# MotorController.net
KiCad netlist of a schematic drawn in EAGLE
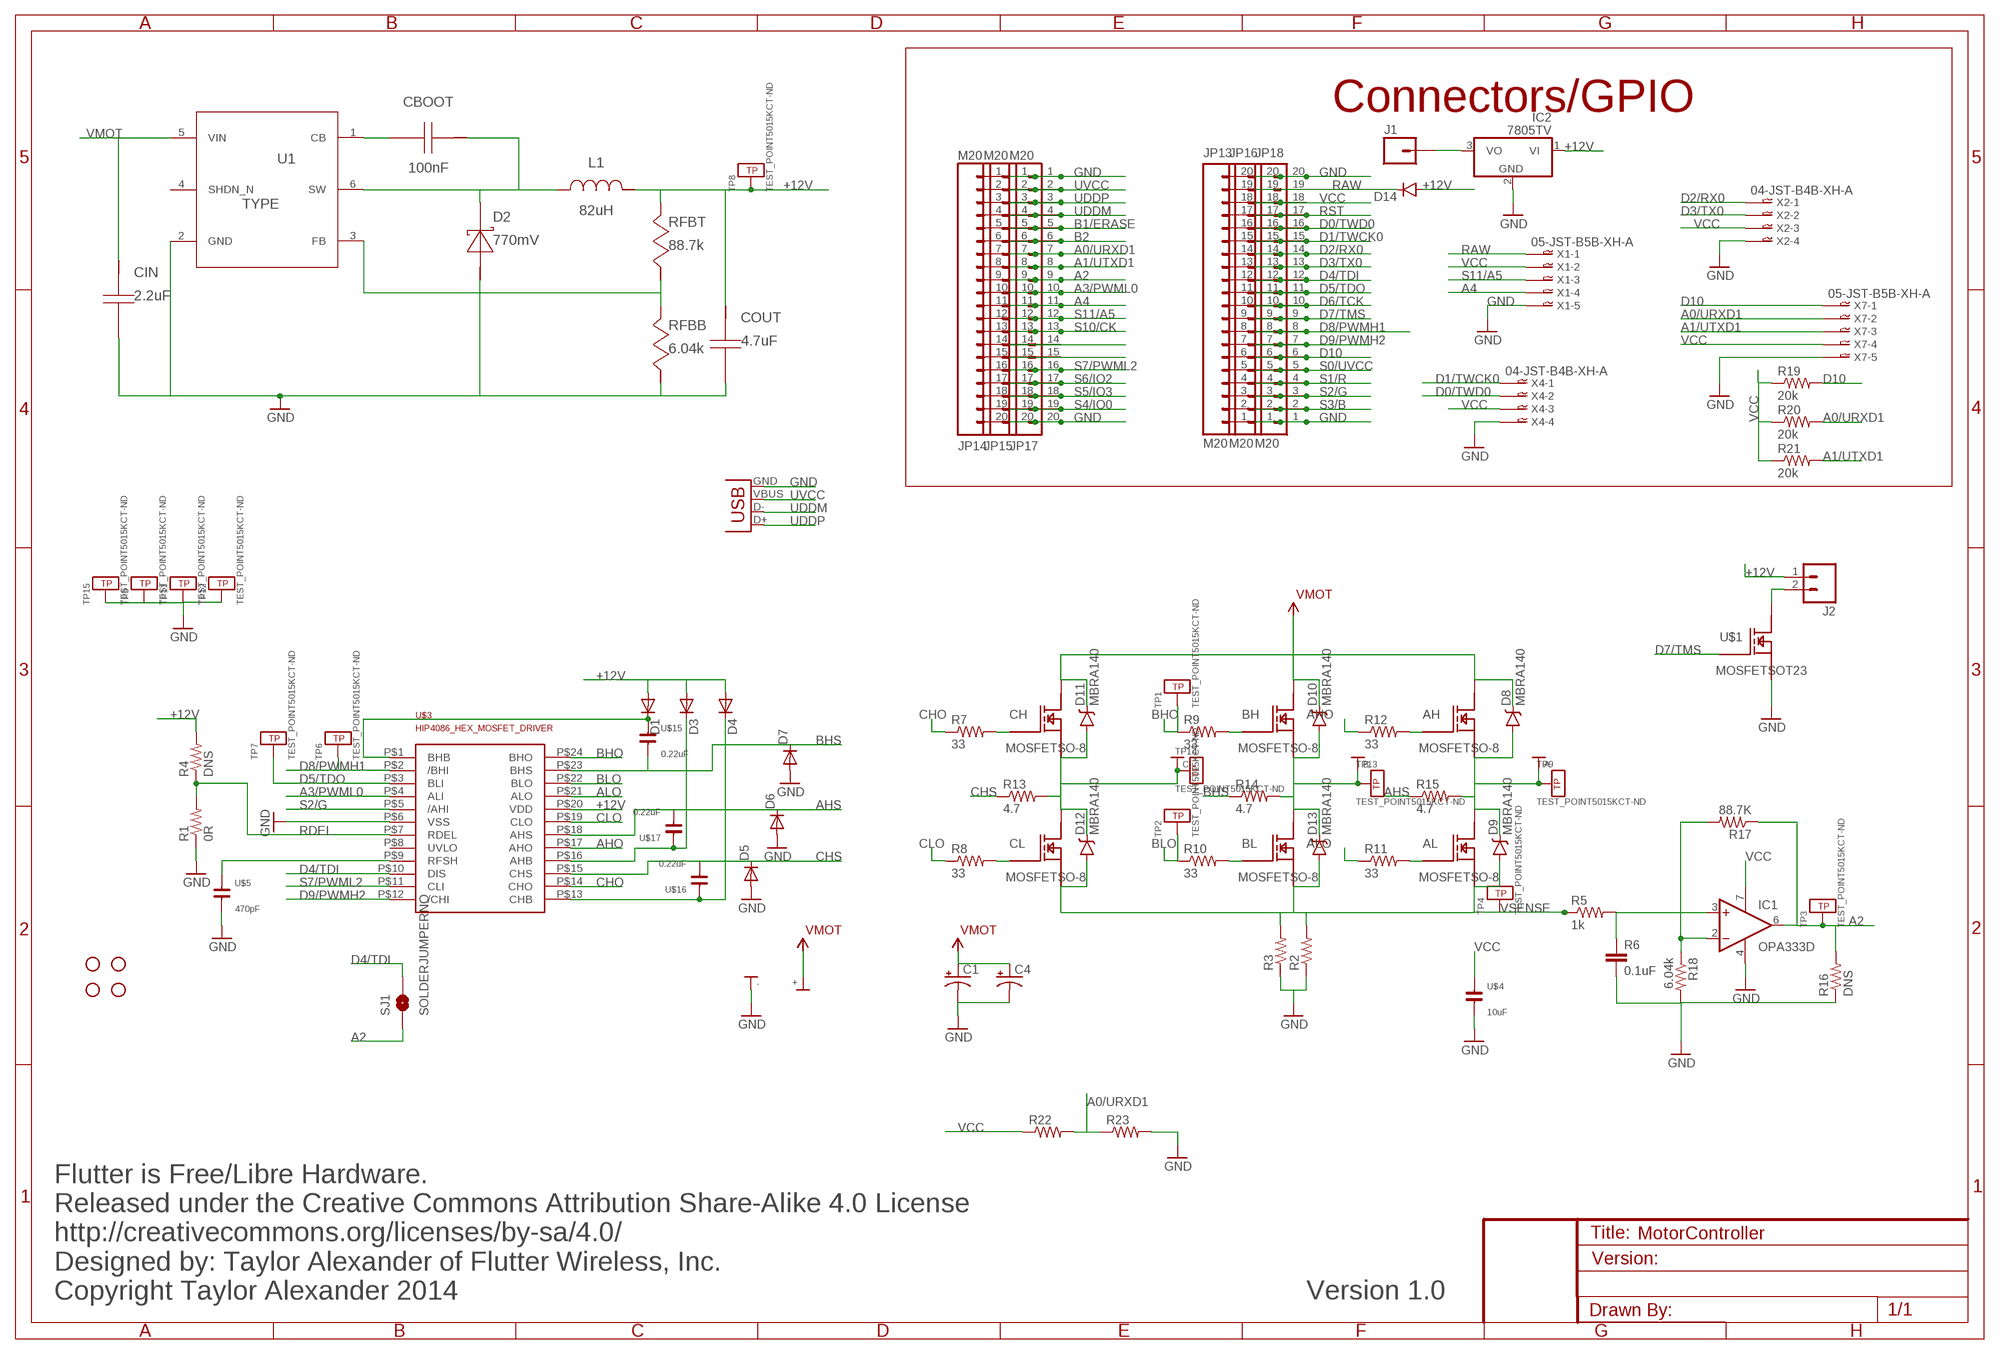
[diagram p0: schematic, sheet 1]

(export (version "E")
  (design (tool "Eeschema 10.0.6"))
  (components
    (comp (ref "+")
      (value "HIGHCURRENTPAD2")
      (footprint "eagle-import:HIGH_CURRENT_PAD2")
      (libsource (lib "eagle-import") (part "HIGHCURRENTPAD2"))
    )
    (comp (ref "-")
      (value "HIGHCURRENTPAD2")
      (footprint "eagle-import:HIGH_CURRENT_PAD2")
      (libsource (lib "eagle-import") (part "HIGHCURRENTPAD2"))
    )
    (comp (ref "A")
      (value "HIGHCURRENTPAD2")
      (footprint "eagle-import:HIGH_CURRENT_PAD2")
      (libsource (lib "eagle-import") (part "HIGHCURRENTPAD2"))
    )
    (comp (ref "AH")
      (value "MOSFETSO-8")
      (footprint "eagle-import:POWERPAK_S0-8")
      (libsource (lib "eagle-import") (part "MOSFETSO-8"))
    )
    (comp (ref "AL")
      (value "MOSFETSO-8")
      (footprint "eagle-import:POWERPAK_S0-8")
      (libsource (lib "eagle-import") (part "MOSFETSO-8"))
    )
    (comp (ref "B")
      (value "HIGHCURRENTPAD2")
      (footprint "eagle-import:HIGH_CURRENT_PAD2")
      (libsource (lib "eagle-import") (part "HIGHCURRENTPAD2"))
    )
    (comp (ref "BH")
      (value "MOSFETSO-8")
      (footprint "eagle-import:POWERPAK_S0-8")
      (libsource (lib "eagle-import") (part "MOSFETSO-8"))
    )
    (comp (ref "BL")
      (value "MOSFETSO-8")
      (footprint "eagle-import:POWERPAK_S0-8")
      (libsource (lib "eagle-import") (part "MOSFETSO-8"))
    )
    (comp (ref "C")
      (value "HIGHCURRENTPAD2")
      (footprint "eagle-import:HIGH_CURRENT_PAD2")
      (libsource (lib "eagle-import") (part "HIGHCURRENTPAD2"))
    )
    (comp (ref "C1")
      (value "CAPACITOR-POLARIZED")
      (footprint "eagle-import:CAP-6.5X18MM")
      (libsource (lib "eagle-import") (part "CAPACITOR-POLARIZED"))
    )
    (comp (ref "C4")
      (value "CAPACITOR-POLARIZED")
      (footprint "eagle-import:CAP-6.5X18MM")
      (libsource (lib "eagle-import") (part "CAPACITOR-POLARIZED"))
    )
    (comp (ref "CBOOT")
      (value "100nF")
      (footprint "eagle-import:0603")
      (fields (field (name "MANUFACTURER_PART_NUMBER") "GRM188R72A104KA35D"))
      (libsource (lib "eagle-import") (part "GRM188R72A104KA35D"))
    )
    (comp (ref "CH")
      (value "MOSFETSO-8")
      (footprint "eagle-import:POWERPAK_S0-8")
      (libsource (lib "eagle-import") (part "MOSFETSO-8"))
    )
    (comp (ref "CIN")
      (value "2.2uF")
      (footprint "eagle-import:1210")
      (fields (field (name "MANUFACTURER_PART_NUMBER") "C3225X7R2A225K230AB"))
      (libsource (lib "eagle-import") (part "C3225X7R2A225K230AB"))
    )
    (comp (ref "CL")
      (value "MOSFETSO-8")
      (footprint "eagle-import:POWERPAK_S0-8")
      (libsource (lib "eagle-import") (part "MOSFETSO-8"))
    )
    (comp (ref "COUT")
      (value "4.7uF")
      (footprint "eagle-import:0805")
      (fields (field (name "MANUFACTURER_PART_NUMBER") "GRM21BR61E475MA12L"))
      (libsource (lib "eagle-import") (part "GRM21BR61E475MA12L"))
    )
    (comp (ref "D1")
      (value "DIODESMA")
      (footprint "eagle-import:SMA-DIODE")
      (libsource (lib "eagle-import") (part "DIODESMA"))
    )
    (comp (ref "D2")
      (value "770mV")
      (footprint "eagle-import:POWERDI123")
      (fields (field (name "MANUFACTURER_PART_NUMBER") "DFLS1100-7"))
      (libsource (lib "eagle-import") (part "DFLS1100-7"))
    )
    (comp (ref "D3")
      (value "DIODESMA")
      (footprint "eagle-import:SMA-DIODE")
      (libsource (lib "eagle-import") (part "DIODESMA"))
    )
    (comp (ref "D4")
      (value "DIODESMA")
      (footprint "eagle-import:SMA-DIODE")
      (libsource (lib "eagle-import") (part "DIODESMA"))
    )
    (comp (ref "D5")
      (value "DIODESMA")
      (footprint "eagle-import:SMA-DIODE")
      (libsource (lib "eagle-import") (part "DIODESMA"))
    )
    (comp (ref "D6")
      (value "DIODESMA")
      (footprint "eagle-import:SMA-DIODE")
      (libsource (lib "eagle-import") (part "DIODESMA"))
    )
    (comp (ref "D7")
      (value "DIODESMA")
      (footprint "eagle-import:SMA-DIODE")
      (libsource (lib "eagle-import") (part "DIODESMA"))
    )
    (comp (ref "D8")
      (value "MBRA140")
      (footprint "eagle-import:SMA-DIODE")
      (libsource (lib "eagle-import") (part "DIODE-SCHOTTKY-MBRA140"))
    )
    (comp (ref "D9")
      (value "MBRA140")
      (footprint "eagle-import:SMA-DIODE")
      (libsource (lib "eagle-import") (part "DIODE-SCHOTTKY-MBRA140"))
    )
    (comp (ref "D10")
      (value "MBRA140")
      (footprint "eagle-import:SMA-DIODE")
      (libsource (lib "eagle-import") (part "DIODE-SCHOTTKY-MBRA140"))
    )
    (comp (ref "D11")
      (value "MBRA140")
      (footprint "eagle-import:SMA-DIODE")
      (libsource (lib "eagle-import") (part "DIODE-SCHOTTKY-MBRA140"))
    )
    (comp (ref "D12")
      (value "MBRA140")
      (footprint "eagle-import:SMA-DIODE")
      (libsource (lib "eagle-import") (part "DIODE-SCHOTTKY-MBRA140"))
    )
    (comp (ref "D13")
      (value "MBRA140")
      (footprint "eagle-import:SMA-DIODE")
      (libsource (lib "eagle-import") (part "DIODE-SCHOTTKY-MBRA140"))
    )
    (comp (ref "D14")
      (value "DIODESOD123")
      (footprint "eagle-import:SOD-123")
      (libsource (lib "eagle-import") (part "DIODESOD123"))
    )
    (comp (ref "IC1")
      (value "OPA333D")
      (footprint "eagle-import:SO08")
      (libsource (lib "eagle-import") (part "OPA333D"))
    )
    (comp (ref "IC2")
      (value "7805TV")
      (footprint "eagle-import:TO220V")
      (libsource (lib "eagle-import") (part "78TV05"))
    )
    (comp (ref "J1")
      (value "M01PTH")
      (footprint "eagle-import:1X01")
      (libsource (lib "eagle-import") (part "M01PTH"))
    )
    (comp (ref "J2")
      (value "M02PTH")
      (footprint "eagle-import:1X02")
      (libsource (lib "eagle-import") (part "M02PTH"))
    )
    (comp (ref "JP13")
      (value "M20")
      (footprint "eagle-import:1X20")
      (libsource (lib "eagle-import") (part "M20"))
    )
    (comp (ref "JP14")
      (value "M20")
      (footprint "eagle-import:1X20")
      (libsource (lib "eagle-import") (part "M20"))
    )
    (comp (ref "JP15")
      (value "M20")
      (footprint "eagle-import:1X20")
      (libsource (lib "eagle-import") (part "M20"))
    )
    (comp (ref "JP16")
      (value "M20")
      (footprint "eagle-import:1X20")
      (libsource (lib "eagle-import") (part "M20"))
    )
    (comp (ref "JP17")
      (value "M20")
      (footprint "eagle-import:1X20")
      (libsource (lib "eagle-import") (part "M20"))
    )
    (comp (ref "JP18")
      (value "M20")
      (footprint "eagle-import:1X20")
      (libsource (lib "eagle-import") (part "M20"))
    )
    (comp (ref "L1")
      (value "82uH")
      (footprint "eagle-import:ME3220")
      (fields (field (name "MANUFACTURER_PART_NUMBER") "ME3220-823KLB"))
      (libsource (lib "eagle-import") (part "ME3220-823KLB"))
    )
    (comp (ref "R1")
      (value "0R")
      (footprint "eagle-import:0603-RES")
      (libsource (lib "eagle-import") (part "RESISTOR0603"))
    )
    (comp (ref "R2")
      (value "RESISTOROHMITE")
      (footprint "eagle-import:OHMITE_FCSL64_CURRENT_SENSE_RESISTOR")
      (libsource (lib "eagle-import") (part "RESISTOROHMITE"))
    )
    (comp (ref "R3")
      (value "RESISTOROHMITE")
      (footprint "eagle-import:OHMITE_FCSL64_CURRENT_SENSE_RESISTOR")
      (libsource (lib "eagle-import") (part "RESISTOROHMITE"))
    )
    (comp (ref "R4")
      (value "DNS")
      (footprint "eagle-import:0603-RES")
      (libsource (lib "eagle-import") (part "RESISTOR0603"))
    )
    (comp (ref "R5")
      (value "1k")
      (footprint "eagle-import:0603-RES")
      (libsource (lib "eagle-import") (part "RESISTOR0603"))
    )
    (comp (ref "R6")
      (value "0.1uF")
      (footprint "eagle-import:0805")
      (libsource (lib "eagle-import") (part "CAP0805"))
    )
    (comp (ref "R7")
      (value "33")
      (footprint "eagle-import:0402-RES")
      (libsource (lib "eagle-import") (part "RESISTOR0402"))
    )
    (comp (ref "R8")
      (value "33")
      (footprint "eagle-import:0402-RES")
      (libsource (lib "eagle-import") (part "RESISTOR0402"))
    )
    (comp (ref "R9")
      (value "33")
      (footprint "eagle-import:0402-RES")
      (libsource (lib "eagle-import") (part "RESISTOR0402"))
    )
    (comp (ref "R10")
      (value "33")
      (footprint "eagle-import:0402-RES")
      (libsource (lib "eagle-import") (part "RESISTOR0402"))
    )
    (comp (ref "R11")
      (value "33")
      (footprint "eagle-import:0402-RES")
      (libsource (lib "eagle-import") (part "RESISTOR0402"))
    )
    (comp (ref "R12")
      (value "33")
      (footprint "eagle-import:0402-RES")
      (libsource (lib "eagle-import") (part "RESISTOR0402"))
    )
    (comp (ref "R13")
      (value "4.7")
      (footprint "eagle-import:0402-RES")
      (libsource (lib "eagle-import") (part "RESISTOR0402"))
    )
    (comp (ref "R14")
      (value "4.7")
      (footprint "eagle-import:0402-RES")
      (libsource (lib "eagle-import") (part "RESISTOR0402"))
    )
    (comp (ref "R15")
      (value "4.7")
      (footprint "eagle-import:0402-RES")
      (libsource (lib "eagle-import") (part "RESISTOR0402"))
    )
    (comp (ref "R16")
      (value "DNS")
      (footprint "eagle-import:0402-RES")
      (libsource (lib "eagle-import") (part "RESISTOR0402"))
    )
    (comp (ref "R17")
      (value "88.7K")
      (footprint "eagle-import:0402-RES")
      (libsource (lib "eagle-import") (part "RESISTOR0402"))
    )
    (comp (ref "R18")
      (value "6.04k")
      (footprint "eagle-import:0402-RES")
      (libsource (lib "eagle-import") (part "RESISTOR0402"))
    )
    (comp (ref "R19")
      (value "20k")
      (footprint "eagle-import:0402-RES")
      (libsource (lib "eagle-import") (part "RESISTOR0402"))
    )
    (comp (ref "R20")
      (value "20k")
      (footprint "eagle-import:0402-RES")
      (libsource (lib "eagle-import") (part "RESISTOR0402"))
    )
    (comp (ref "R21")
      (value "20k")
      (footprint "eagle-import:0402-RES")
      (libsource (lib "eagle-import") (part "RESISTOR0402"))
    )
    (comp (ref "R22")
      (value "RESISTOR0603")
      (footprint "eagle-import:0603-RES")
      (libsource (lib "eagle-import") (part "RESISTOR0603"))
    )
    (comp (ref "R23")
      (value "RESISTOR0603")
      (footprint "eagle-import:0603-RES")
      (libsource (lib "eagle-import") (part "RESISTOR0603"))
    )
    (comp (ref "RFBB")
      (value "6.04k")
      (footprint "eagle-import:0402")
      (fields
        (field (name "MANUFACTURER_PART_NUMBER") "CRCW04026K04FKED")
        (field (name "POWER") "0.063")
        (field (name "TOLERANCE") "1.0")
      )
      (libsource (lib "eagle-import") (part "CRCW04026K04FKED"))
    )
    (comp (ref "RFBT")
      (value "88.7k")
      (footprint "eagle-import:0402")
      (fields
        (field (name "MANUFACTURER_PART_NUMBER") "CRCW040288K7FKED")
        (field (name "POWER") "0.063")
        (field (name "TOLERANCE") "1.0")
      )
      (libsource (lib "eagle-import") (part "CRCW040288K7FKED"))
    )
    (comp (ref "SJ1")
      (value "SOLDERJUMPERNO")
      (footprint "eagle-import:SJ_2S-NO")
      (libsource (lib "eagle-import") (part "SOLDERJUMPERNO"))
    )
    (comp (ref "STANDOFF1")
      (value "STAND-OFF")
      (footprint "eagle-import:STAND-OFF")
      (libsource (lib "eagle-import") (part "STAND-OFF"))
    )
    (comp (ref "STANDOFF2")
      (value "STAND-OFF")
      (footprint "eagle-import:STAND-OFF")
      (libsource (lib "eagle-import") (part "STAND-OFF"))
    )
    (comp (ref "STANDOFF3")
      (value "STAND-OFF")
      (footprint "eagle-import:STAND-OFF")
      (libsource (lib "eagle-import") (part "STAND-OFF"))
    )
    (comp (ref "STANDOFF4")
      (value "STAND-OFF")
      (footprint "eagle-import:STAND-OFF")
      (libsource (lib "eagle-import") (part "STAND-OFF"))
    )
    (comp (ref "TP1")
      (value "TEST_POINT5015KCT-ND")
      (footprint "eagle-import:TEST_POINT_SMT_KEYSTONE_5015")
      (libsource (lib "eagle-import") (part "TEST_POINT5015KCT-ND"))
    )
    (comp (ref "TP2")
      (value "TEST_POINT5015KCT-ND")
      (footprint "eagle-import:TEST_POINT_SMT_KEYSTONE_5015")
      (libsource (lib "eagle-import") (part "TEST_POINT5015KCT-ND"))
    )
    (comp (ref "TP3")
      (value "TEST_POINT5015KCT-ND")
      (footprint "eagle-import:TEST_POINT_SMT_KEYSTONE_5015")
      (libsource (lib "eagle-import") (part "TEST_POINT5015KCT-ND"))
    )
    (comp (ref "TP4")
      (value "TEST_POINT5015KCT-ND")
      (footprint "eagle-import:TEST_POINT_SMT_KEYSTONE_5015")
      (libsource (lib "eagle-import") (part "TEST_POINT5015KCT-ND"))
    )
    (comp (ref "TP5")
      (value "TEST_POINT5015KCT-ND")
      (footprint "eagle-import:TEST_POINT_SMT_KEYSTONE_5015")
      (libsource (lib "eagle-import") (part "TEST_POINT5015KCT-ND"))
    )
    (comp (ref "TP6")
      (value "TEST_POINT5015KCT-ND")
      (footprint "eagle-import:TEST_POINT_SMT_KEYSTONE_5015")
      (libsource (lib "eagle-import") (part "TEST_POINT5015KCT-ND"))
    )
    (comp (ref "TP7")
      (value "TEST_POINT5015KCT-ND")
      (footprint "eagle-import:TEST_POINT_SMT_KEYSTONE_5015")
      (libsource (lib "eagle-import") (part "TEST_POINT5015KCT-ND"))
    )
    (comp (ref "TP8")
      (value "TEST_POINT5015KCT-ND")
      (footprint "eagle-import:TEST_POINT_SMT_KEYSTONE_5015")
      (libsource (lib "eagle-import") (part "TEST_POINT5015KCT-ND"))
    )
    (comp (ref "TP9")
      (value "TEST_POINT5015KCT-ND")
      (footprint "eagle-import:TEST_POINT_SMT_KEYSTONE_5015")
      (libsource (lib "eagle-import") (part "TEST_POINT5015KCT-ND"))
    )
    (comp (ref "TP11")
      (value "TEST_POINT5015KCT-ND")
      (footprint "eagle-import:TEST_POINT_SMT_KEYSTONE_5015")
      (libsource (lib "eagle-import") (part "TEST_POINT5015KCT-ND"))
    )
    (comp (ref "TP12")
      (value "TEST_POINT5015KCT-ND")
      (footprint "eagle-import:TEST_POINT_SMT_KEYSTONE_5015")
      (libsource (lib "eagle-import") (part "TEST_POINT5015KCT-ND"))
    )
    (comp (ref "TP13")
      (value "TEST_POINT5015KCT-ND")
      (footprint "eagle-import:TEST_POINT_SMT_KEYSTONE_5015")
      (libsource (lib "eagle-import") (part "TEST_POINT5015KCT-ND"))
    )
    (comp (ref "TP14")
      (value "TEST_POINT5015KCT-ND")
      (footprint "eagle-import:TEST_POINT_SMT_KEYSTONE_5015")
      (libsource (lib "eagle-import") (part "TEST_POINT5015KCT-ND"))
    )
    (comp (ref "TP15")
      (value "TEST_POINT5015KCT-ND")
      (footprint "eagle-import:TEST_POINT_SMT_KEYSTONE_5015")
      (libsource (lib "eagle-import") (part "TEST_POINT5015KCT-ND"))
    )
    (comp (ref "U$1")
      (value "MOSFETSOT23")
      (footprint "eagle-import:SOT23")
      (libsource (lib "eagle-import") (part "MOSFETSOT23"))
    )
    (comp (ref "U$3")
      (value "HIP4086_HEX_MOSFET_DRIVER")
      (footprint "eagle-import:SOIC-24")
      (libsource (lib "eagle-import") (part "HIP4086_HEX_MOSFET_DRIVER"))
    )
    (comp (ref "U$4")
      (value "10uF")
      (footprint "eagle-import:0808-CAP")
      (libsource (lib "eagle-import") (part "CAPACITOR0805"))
    )
    (comp (ref "U$5")
      (value "470pF")
      (footprint "eagle-import:0603-CAP")
      (libsource (lib "eagle-import") (part "CAPACITOR0603-CAP"))
    )
    (comp (ref "U$15")
      (value "0.22uF")
      (footprint "eagle-import:0808-CAP")
      (libsource (lib "eagle-import") (part "CAPACITOR0805"))
    )
    (comp (ref "U$16")
      (value "0.22uF")
      (footprint "eagle-import:0808-CAP")
      (libsource (lib "eagle-import") (part "CAPACITOR0805"))
    )
    (comp (ref "U$17")
      (value "0.22uF")
      (footprint "eagle-import:0808-CAP")
      (libsource (lib "eagle-import") (part "CAPACITOR0805"))
    )
    (comp (ref "U1")
      (value "Value")
      (footprint "eagle-import:DDC0006A")
      (fields
        (field (name "MANUFACTURER") "Texas Instruments")
        (field (name "MANUFACTURER_PART_NUMBER") "LMR16006YDDCR")
        (field (name "PARTNUMBER") "LMR16006YDDC")
        (field (name "TYPE") "TYPE")
      )
      (libsource (lib "eagle-import") (part "LMR16006YDDCR"))
    )
    (comp (ref "X1")
      (value "05-JST-B5B-XH-A")
      (footprint "eagle-import:B5B-XH")
      (libsource (lib "eagle-import") (part "05-JST-B5B-XH-A"))
    )
    (comp (ref "X2")
      (value "04-JST-B4B-XH-A")
      (footprint "eagle-import:B4B-XH")
      (libsource (lib "eagle-import") (part "04-JST-B4B-XH-A"))
    )
    (comp (ref "X4")
      (value "04-JST-B4B-XH-A")
      (footprint "eagle-import:B4B-XH")
      (libsource (lib "eagle-import") (part "04-JST-B4B-XH-A"))
    )
    (comp (ref "X5")
      (value "USBPTH")
      (footprint "eagle-import:USB-B-PTH")
      (libsource (lib "eagle-import") (part "USBPTH"))
    )
    (comp (ref "X7")
      (value "05-JST-B5B-XH-A")
      (footprint "eagle-import:B5B-XH")
      (libsource (lib "eagle-import") (part "05-JST-B5B-XH-A"))
    )
  )
  (nets
    (net (code "1") (name "/+12V") (class "Default")
      (node (ref "COUT") (pin "1") (pinfunction "1_1") (pintype "passive"))
      (node (ref "D1") (pin "A") (pinfunction "A_A") (pintype "passive"))
      (node (ref "D14") (pin "A") (pinfunction "A_A") (pintype "passive"))
      (node (ref "D3") (pin "A") (pinfunction "A_A") (pintype "passive"))
      (node (ref "D4") (pin "A") (pinfunction "A_A") (pintype "passive"))
      (node (ref "IC2") (pin "1") (pinfunction "VI_1") (pintype "input"))
      (node (ref "J2") (pin "1") (pinfunction "1_1") (pintype "passive"))
      (node (ref "L1") (pin "2") (pinfunction "2_2") (pintype "passive"))
      (node (ref "R4") (pin "2") (pinfunction "2_2") (pintype "passive"))
      (node (ref "RFBT") (pin "1") (pinfunction "1_1") (pintype "passive"))
      (node (ref "TP8") (pin "P$1") (pinfunction "P$1_P$1") (pintype "bidirectional"))
      (node (ref "U$3") (pin "P$20") (pinfunction "VDD_P$20") (pintype "bidirectional"))
    )
    (net (code "2") (name "/A0{slash}URXD1") (class "Default")
      (node (ref "JP14") (pin "7") (pinfunction "7_7") (pintype "passive"))
      (node (ref "JP15") (pin "7") (pinfunction "7_7") (pintype "passive"))
      (node (ref "JP17") (pin "7") (pinfunction "7_7") (pintype "passive"))
      (node (ref "R20") (pin "2") (pinfunction "2_2") (pintype "passive"))
      (node (ref "R22") (pin "2") (pinfunction "2_2") (pintype "passive"))
      (node (ref "R23") (pin "1") (pinfunction "1_1") (pintype "passive"))
      (node (ref "X7") (pin "P$2") (pinfunction "1_P$2") (pintype "passive"))
    )
    (net (code "3") (name "/A1{slash}UTXD1") (class "Default")
      (node (ref "JP14") (pin "8") (pinfunction "8_8") (pintype "passive"))
      (node (ref "JP15") (pin "8") (pinfunction "8_8") (pintype "passive"))
      (node (ref "JP17") (pin "8") (pinfunction "8_8") (pintype "passive"))
      (node (ref "R21") (pin "2") (pinfunction "2_2") (pintype "passive"))
      (node (ref "X7") (pin "P$3") (pinfunction "1_P$3") (pintype "passive"))
    )
    (net (code "4") (name "/A2") (class "Default")
      (node (ref "IC1") (pin "6") (pinfunction "OUT_6") (pintype "output"))
      (node (ref "JP14") (pin "9") (pinfunction "9_9") (pintype "passive"))
      (node (ref "JP15") (pin "9") (pinfunction "9_9") (pintype "passive"))
      (node (ref "JP17") (pin "9") (pinfunction "9_9") (pintype "passive"))
      (node (ref "R16") (pin "2") (pinfunction "2_2") (pintype "passive"))
      (node (ref "R17") (pin "1") (pinfunction "1_1") (pintype "passive"))
      (node (ref "SJ1") (pin "1") (pinfunction "1_1") (pintype "passive"))
      (node (ref "TP3") (pin "P$1") (pinfunction "P$1_P$1") (pintype "bidirectional"))
    )
    (net (code "5") (name "/A3{slash}PWML0") (class "Default")
      (node (ref "JP14") (pin "10") (pinfunction "10_10") (pintype "passive"))
      (node (ref "JP15") (pin "10") (pinfunction "10_10") (pintype "passive"))
      (node (ref "JP17") (pin "10") (pinfunction "10_10") (pintype "passive"))
      (node (ref "U$3") (pin "P$4") (pinfunction "ALI_P$4") (pintype "bidirectional"))
    )
    (net (code "6") (name "/A4") (class "Default")
      (node (ref "JP14") (pin "11") (pinfunction "11_11") (pintype "passive"))
      (node (ref "JP15") (pin "11") (pinfunction "11_11") (pintype "passive"))
      (node (ref "JP17") (pin "11") (pinfunction "11_11") (pintype "passive"))
      (node (ref "X1") (pin "P$4") (pinfunction "1_P$4") (pintype "passive"))
    )
    (net (code "7") (name "/AHO") (class "Default")
      (node (ref "R12") (pin "1") (pinfunction "1_1") (pintype "passive"))
      (node (ref "U$3") (pin "P$17") (pinfunction "AHO_P$17") (pintype "bidirectional"))
    )
    (net (code "8") (name "/AHS") (class "Default")
      (node (ref "D6") (pin "C") (pinfunction "C_C") (pintype "passive"))
      (node (ref "R15") (pin "1") (pinfunction "1_1") (pintype "passive"))
      (node (ref "U$17") (pin "2") (pinfunction "2_2") (pintype "bidirectional"))
      (node (ref "U$3") (pin "P$18") (pinfunction "AHS_P$18") (pintype "bidirectional"))
    )
    (net (code "9") (name "/ALO") (class "Default")
      (node (ref "R11") (pin "1") (pinfunction "1_1") (pintype "passive"))
      (node (ref "U$3") (pin "P$21") (pinfunction "ALO_P$21") (pintype "bidirectional"))
    )
    (net (code "10") (name "/B1{slash}ERASE") (class "Default")
      (node (ref "JP14") (pin "5") (pinfunction "5_5") (pintype "passive"))
      (node (ref "JP15") (pin "5") (pinfunction "5_5") (pintype "passive"))
      (node (ref "JP17") (pin "5") (pinfunction "5_5") (pintype "passive"))
    )
    (net (code "11") (name "/B2") (class "Default")
      (node (ref "JP14") (pin "6") (pinfunction "6_6") (pintype "passive"))
      (node (ref "JP15") (pin "6") (pinfunction "6_6") (pintype "passive"))
      (node (ref "JP17") (pin "6") (pinfunction "6_6") (pintype "passive"))
    )
    (net (code "12") (name "/BHO") (class "Default")
      (node (ref "R9") (pin "1") (pinfunction "1_1") (pintype "passive"))
      (node (ref "TP1") (pin "P$1") (pinfunction "P$1_P$1") (pintype "bidirectional"))
      (node (ref "U$3") (pin "P$24") (pinfunction "BHO_P$24") (pintype "bidirectional"))
    )
    (net (code "13") (name "/BHS") (class "Default")
      (node (ref "D7") (pin "C") (pinfunction "C_C") (pintype "passive"))
      (node (ref "R14") (pin "1") (pinfunction "1_1") (pintype "passive"))
      (node (ref "U$15") (pin "2") (pinfunction "2_2") (pintype "bidirectional"))
      (node (ref "U$3") (pin "P$23") (pinfunction "BHS_P$23") (pintype "bidirectional"))
    )
    (net (code "14") (name "/BLO") (class "Default")
      (node (ref "R10") (pin "1") (pinfunction "1_1") (pintype "passive"))
      (node (ref "TP2") (pin "P$1") (pinfunction "P$1_P$1") (pintype "bidirectional"))
      (node (ref "U$3") (pin "P$22") (pinfunction "BLO_P$22") (pintype "bidirectional"))
    )
    (net (code "15") (name "/CHO") (class "Default")
      (node (ref "R7") (pin "1") (pinfunction "1_1") (pintype "passive"))
      (node (ref "U$3") (pin "P$14") (pinfunction "CHO_P$14") (pintype "bidirectional"))
    )
    (net (code "16") (name "/CHS") (class "Default")
      (node (ref "D5") (pin "C") (pinfunction "C_C") (pintype "passive"))
      (node (ref "R13") (pin "1") (pinfunction "1_1") (pintype "passive"))
      (node (ref "U$16") (pin "2") (pinfunction "2_2") (pintype "bidirectional"))
      (node (ref "U$3") (pin "P$15") (pinfunction "CHS_P$15") (pintype "bidirectional"))
    )
    (net (code "17") (name "/CLO") (class "Default")
      (node (ref "R8") (pin "1") (pinfunction "1_1") (pintype "passive"))
      (node (ref "U$3") (pin "P$19") (pinfunction "CLO_P$19") (pintype "bidirectional"))
    )
    (net (code "18") (name "/D0{slash}TWD0") (class "Default")
      (node (ref "JP13") (pin "16") (pinfunction "16_16") (pintype "passive"))
      (node (ref "JP16") (pin "16") (pinfunction "16_16") (pintype "passive"))
      (node (ref "JP18") (pin "16") (pinfunction "16_16") (pintype "passive"))
      (node (ref "X4") (pin "P$2") (pinfunction "1_P$2") (pintype "passive"))
    )
    (net (code "19") (name "/D1{slash}TWCK0") (class "Default")
      (node (ref "JP13") (pin "15") (pinfunction "15_15") (pintype "passive"))
      (node (ref "JP16") (pin "15") (pinfunction "15_15") (pintype "passive"))
      (node (ref "JP18") (pin "15") (pinfunction "15_15") (pintype "passive"))
      (node (ref "X4") (pin "P$1") (pinfunction "1_P$1") (pintype "passive"))
    )
    (net (code "20") (name "/D2{slash}RX0") (class "Default")
      (node (ref "JP13") (pin "14") (pinfunction "14_14") (pintype "passive"))
      (node (ref "JP16") (pin "14") (pinfunction "14_14") (pintype "passive"))
      (node (ref "JP18") (pin "14") (pinfunction "14_14") (pintype "passive"))
      (node (ref "X2") (pin "P$1") (pinfunction "1_P$1") (pintype "passive"))
    )
    (net (code "21") (name "/D3{slash}TX0") (class "Default")
      (node (ref "JP13") (pin "13") (pinfunction "13_13") (pintype "passive"))
      (node (ref "JP16") (pin "13") (pinfunction "13_13") (pintype "passive"))
      (node (ref "JP18") (pin "13") (pinfunction "13_13") (pintype "passive"))
      (node (ref "X2") (pin "P$2") (pinfunction "1_P$2") (pintype "passive"))
    )
    (net (code "22") (name "/D4{slash}TDI") (class "Default")
      (node (ref "JP13") (pin "12") (pinfunction "12_12") (pintype "passive"))
      (node (ref "JP16") (pin "12") (pinfunction "12_12") (pintype "passive"))
      (node (ref "JP18") (pin "12") (pinfunction "12_12") (pintype "passive"))
      (node (ref "SJ1") (pin "2") (pinfunction "2_2") (pintype "passive"))
      (node (ref "U$3") (pin "P$10") (pinfunction "DIS_P$10") (pintype "bidirectional"))
    )
    (net (code "23") (name "/D5{slash}TDO") (class "Default")
      (node (ref "JP13") (pin "11") (pinfunction "11_11") (pintype "passive"))
      (node (ref "JP16") (pin "11") (pinfunction "11_11") (pintype "passive"))
      (node (ref "JP18") (pin "11") (pinfunction "11_11") (pintype "passive"))
      (node (ref "TP7") (pin "P$1") (pinfunction "P$1_P$1") (pintype "bidirectional"))
      (node (ref "U$3") (pin "P$3") (pinfunction "BLI_P$3") (pintype "bidirectional"))
    )
    (net (code "24") (name "/D6{slash}TCK") (class "Default")
      (node (ref "JP13") (pin "10") (pinfunction "10_10") (pintype "passive"))
      (node (ref "JP16") (pin "10") (pinfunction "10_10") (pintype "passive"))
      (node (ref "JP18") (pin "10") (pinfunction "10_10") (pintype "passive"))
    )
    (net (code "25") (name "/D7{slash}TMS") (class "Default")
      (node (ref "JP13") (pin "9") (pinfunction "9_9") (pintype "passive"))
      (node (ref "JP16") (pin "9") (pinfunction "9_9") (pintype "passive"))
      (node (ref "JP18") (pin "9") (pinfunction "9_9") (pintype "passive"))
      (node (ref "U$1") (pin "1") (pinfunction "G_1") (pintype "bidirectional"))
    )
    (net (code "26") (name "/D8{slash}PWMH1") (class "Default")
      (node (ref "JP13") (pin "8") (pinfunction "8_8") (pintype "passive"))
      (node (ref "JP16") (pin "8") (pinfunction "8_8") (pintype "passive"))
      (node (ref "JP18") (pin "8") (pinfunction "8_8") (pintype "passive"))
      (node (ref "TP6") (pin "P$1") (pinfunction "P$1_P$1") (pintype "bidirectional"))
      (node (ref "U$3") (pin "P$2") (pinfunction "/BHI_P$2") (pintype "bidirectional"))
    )
    (net (code "27") (name "/D9{slash}PWMH2") (class "Default")
      (node (ref "JP13") (pin "7") (pinfunction "7_7") (pintype "passive"))
      (node (ref "JP16") (pin "7") (pinfunction "7_7") (pintype "passive"))
      (node (ref "JP18") (pin "7") (pinfunction "7_7") (pintype "passive"))
      (node (ref "U$3") (pin "P$12") (pinfunction "/CHI_P$12") (pintype "bidirectional"))
    )
    (net (code "28") (name "/D10") (class "Default")
      (node (ref "JP13") (pin "6") (pinfunction "6_6") (pintype "passive"))
      (node (ref "JP16") (pin "6") (pinfunction "6_6") (pintype "passive"))
      (node (ref "JP18") (pin "6") (pinfunction "6_6") (pintype "passive"))
      (node (ref "R19") (pin "2") (pinfunction "2_2") (pintype "passive"))
      (node (ref "X7") (pin "P$1") (pinfunction "1_P$1") (pintype "passive"))
    )
    (net (code "29") (name "/RAW") (class "Default")
      (node (ref "D14") (pin "C") (pinfunction "C_C") (pintype "passive"))
      (node (ref "JP13") (pin "19") (pinfunction "19_19") (pintype "passive"))
      (node (ref "JP16") (pin "19") (pinfunction "19_19") (pintype "passive"))
      (node (ref "JP18") (pin "19") (pinfunction "19_19") (pintype "passive"))
      (node (ref "X1") (pin "P$1") (pinfunction "1_P$1") (pintype "passive"))
    )
    (net (code "30") (name "/RDEL") (class "Default")
      (node (ref "R1") (pin "2") (pinfunction "2_2") (pintype "passive"))
      (node (ref "R4") (pin "1") (pinfunction "1_1") (pintype "passive"))
      (node (ref "U$3") (pin "P$7") (pinfunction "RDEL_P$7") (pintype "bidirectional"))
    )
    (net (code "31") (name "/RST") (class "Default")
      (node (ref "JP13") (pin "17") (pinfunction "17_17") (pintype "passive"))
      (node (ref "JP16") (pin "17") (pinfunction "17_17") (pintype "passive"))
      (node (ref "JP18") (pin "17") (pinfunction "17_17") (pintype "passive"))
    )
    (net (code "32") (name "/S0{slash}UVCC") (class "Default")
      (node (ref "JP13") (pin "5") (pinfunction "5_5") (pintype "passive"))
      (node (ref "JP16") (pin "5") (pinfunction "5_5") (pintype "passive"))
      (node (ref "JP18") (pin "5") (pinfunction "5_5") (pintype "passive"))
    )
    (net (code "33") (name "/S1{slash}R") (class "Default")
      (node (ref "JP13") (pin "4") (pinfunction "4_4") (pintype "passive"))
      (node (ref "JP16") (pin "4") (pinfunction "4_4") (pintype "passive"))
      (node (ref "JP18") (pin "4") (pinfunction "4_4") (pintype "passive"))
    )
    (net (code "34") (name "/S2{slash}G") (class "Default")
      (node (ref "JP13") (pin "3") (pinfunction "3_3") (pintype "passive"))
      (node (ref "JP16") (pin "3") (pinfunction "3_3") (pintype "passive"))
      (node (ref "JP18") (pin "3") (pinfunction "3_3") (pintype "passive"))
      (node (ref "U$3") (pin "P$5") (pinfunction "/AHI_P$5") (pintype "bidirectional"))
    )
    (net (code "35") (name "/S3{slash}B") (class "Default")
      (node (ref "JP13") (pin "2") (pinfunction "2_2") (pintype "passive"))
      (node (ref "JP16") (pin "2") (pinfunction "2_2") (pintype "passive"))
      (node (ref "JP18") (pin "2") (pinfunction "2_2") (pintype "passive"))
    )
    (net (code "36") (name "/S4{slash}IO0") (class "Default")
      (node (ref "JP14") (pin "19") (pinfunction "19_19") (pintype "passive"))
      (node (ref "JP15") (pin "19") (pinfunction "19_19") (pintype "passive"))
      (node (ref "JP17") (pin "19") (pinfunction "19_19") (pintype "passive"))
    )
    (net (code "37") (name "/S5{slash}IO3") (class "Default")
      (node (ref "JP14") (pin "18") (pinfunction "18_18") (pintype "passive"))
      (node (ref "JP15") (pin "18") (pinfunction "18_18") (pintype "passive"))
      (node (ref "JP17") (pin "18") (pinfunction "18_18") (pintype "passive"))
    )
    (net (code "38") (name "/S6{slash}IO2") (class "Default")
      (node (ref "JP14") (pin "17") (pinfunction "17_17") (pintype "passive"))
      (node (ref "JP15") (pin "17") (pinfunction "17_17") (pintype "passive"))
      (node (ref "JP17") (pin "17") (pinfunction "17_17") (pintype "passive"))
    )
    (net (code "39") (name "/S7{slash}PWML2") (class "Default")
      (node (ref "JP14") (pin "16") (pinfunction "16_16") (pintype "passive"))
      (node (ref "JP15") (pin "16") (pinfunction "16_16") (pintype "passive"))
      (node (ref "JP17") (pin "16") (pinfunction "16_16") (pintype "passive"))
      (node (ref "U$3") (pin "P$11") (pinfunction "CLI_P$11") (pintype "bidirectional"))
    )
    (net (code "40") (name "/S10{slash}CK") (class "Default")
      (node (ref "JP14") (pin "13") (pinfunction "13_13") (pintype "passive"))
      (node (ref "JP15") (pin "13") (pinfunction "13_13") (pintype "passive"))
      (node (ref "JP17") (pin "13") (pinfunction "13_13") (pintype "passive"))
    )
    (net (code "41") (name "/S11{slash}A5") (class "Default")
      (node (ref "JP14") (pin "12") (pinfunction "12_12") (pintype "passive"))
      (node (ref "JP15") (pin "12") (pinfunction "12_12") (pintype "passive"))
      (node (ref "JP17") (pin "12") (pinfunction "12_12") (pintype "passive"))
      (node (ref "X1") (pin "P$3") (pinfunction "1_P$3") (pintype "passive"))
    )
    (net (code "42") (name "/UDDM") (class "Default")
      (node (ref "JP14") (pin "4") (pinfunction "4_4") (pintype "passive"))
      (node (ref "JP15") (pin "4") (pinfunction "4_4") (pintype "passive"))
      (node (ref "JP17") (pin "4") (pinfunction "4_4") (pintype "passive"))
      (node (ref "X5") (pin "D-") (pinfunction "D-_D-") (pintype "bidirectional"))
    )
    (net (code "43") (name "/UDDP") (class "Default")
      (node (ref "JP14") (pin "3") (pinfunction "3_3") (pintype "passive"))
      (node (ref "JP15") (pin "3") (pinfunction "3_3") (pintype "passive"))
      (node (ref "JP17") (pin "3") (pinfunction "3_3") (pintype "passive"))
      (node (ref "X5") (pin "D+") (pinfunction "D+_D+") (pintype "bidirectional"))
    )
    (net (code "44") (name "/UVCC") (class "Default")
      (node (ref "JP14") (pin "2") (pinfunction "2_2") (pintype "passive"))
      (node (ref "JP15") (pin "2") (pinfunction "2_2") (pintype "passive"))
      (node (ref "JP17") (pin "2") (pinfunction "2_2") (pintype "passive"))
      (node (ref "X5") (pin "VBUS") (pinfunction "VBUS_VBUS") (pintype "bidirectional"))
    )
    (net (code "45") (name "/VCC") (class "Default")
      (node (ref "IC1") (pin "7") (pinfunction "V+_7") (pintype "power_in"))
      (node (ref "JP13") (pin "18") (pinfunction "18_18") (pintype "passive"))
      (node (ref "JP16") (pin "18") (pinfunction "18_18") (pintype "passive"))
      (node (ref "JP18") (pin "18") (pinfunction "18_18") (pintype "passive"))
      (node (ref "R19") (pin "1") (pinfunction "1_1") (pintype "passive"))
      (node (ref "R20") (pin "1") (pinfunction "1_1") (pintype "passive"))
      (node (ref "R21") (pin "1") (pinfunction "1_1") (pintype "passive"))
      (node (ref "R22") (pin "1") (pinfunction "1_1") (pintype "passive"))
      (node (ref "U$4") (pin "1") (pinfunction "1_1") (pintype "bidirectional"))
      (node (ref "X1") (pin "P$2") (pinfunction "1_P$2") (pintype "passive"))
      (node (ref "X2") (pin "P$3") (pinfunction "1_P$3") (pintype "passive"))
      (node (ref "X4") (pin "P$3") (pinfunction "1_P$3") (pintype "passive"))
      (node (ref "X7") (pin "P$4") (pinfunction "1_P$4") (pintype "passive"))
    )
    (net (code "46") (name "/VSENSE") (class "Default")
      (node (ref "AL") (pin "S@1") (pinfunction "S_S@1") (pintype "bidirectional"))
      (node (ref "AL") (pin "S@2") (pinfunction "S_S@2") (pintype "bidirectional"))
      (node (ref "AL") (pin "S@3") (pinfunction "S_S@3") (pintype "bidirectional"))
      (node (ref "BL") (pin "S@1") (pinfunction "S_S@1") (pintype "bidirectional"))
      (node (ref "BL") (pin "S@2") (pinfunction "S_S@2") (pintype "bidirectional"))
      (node (ref "BL") (pin "S@3") (pinfunction "S_S@3") (pintype "bidirectional"))
      (node (ref "CL") (pin "S@1") (pinfunction "S_S@1") (pintype "bidirectional"))
      (node (ref "CL") (pin "S@2") (pinfunction "S_S@2") (pintype "bidirectional"))
      (node (ref "CL") (pin "S@3") (pinfunction "S_S@3") (pintype "bidirectional"))
      (node (ref "D12") (pin "A") (pinfunction "A_A") (pintype "passive"))
      (node (ref "D13") (pin "A") (pinfunction "A_A") (pintype "passive"))
      (node (ref "D9") (pin "A") (pinfunction "A_A") (pintype "passive"))
      (node (ref "R2") (pin "P$2") (pinfunction "2_P$2") (pintype "passive"))
      (node (ref "R3") (pin "P$2") (pinfunction "2_P$2") (pintype "passive"))
      (node (ref "R5") (pin "1") (pinfunction "1_1") (pintype "passive"))
      (node (ref "TP4") (pin "P$1") (pinfunction "P$1_P$1") (pintype "bidirectional"))
    )
    (net (code "47") (name "GND") (class "Default")
      (node (ref "-") (pin "P$1") (pinfunction "P$1_P$1") (pintype "bidirectional"))
      (node (ref "C1") (pin "-") (pinfunction "-_-") (pintype "passive"))
      (node (ref "C4") (pin "-") (pinfunction "-_-") (pintype "passive"))
      (node (ref "CIN") (pin "2") (pinfunction "2_2") (pintype "passive"))
      (node (ref "COUT") (pin "2") (pinfunction "2_2") (pintype "passive"))
      (node (ref "D2") (pin "2") (pinfunction "A_2") (pintype "passive"))
      (node (ref "D5") (pin "A") (pinfunction "A_A") (pintype "passive"))
      (node (ref "D6") (pin "A") (pinfunction "A_A") (pintype "passive"))
      (node (ref "D7") (pin "A") (pinfunction "A_A") (pintype "passive"))
      (node (ref "IC1") (pin "4") (pinfunction "V-_4") (pintype "power_in"))
      (node (ref "IC2") (pin "2") (pinfunction "GND_2") (pintype "passive"))
      (node (ref "JP13") (pin "1") (pinfunction "1_1") (pintype "passive"))
      (node (ref "JP13") (pin "20") (pinfunction "20_20") (pintype "passive"))
      (node (ref "JP14") (pin "1") (pinfunction "1_1") (pintype "passive"))
      (node (ref "JP14") (pin "20") (pinfunction "20_20") (pintype "passive"))
      (node (ref "JP15") (pin "1") (pinfunction "1_1") (pintype "passive"))
      (node (ref "JP15") (pin "20") (pinfunction "20_20") (pintype "passive"))
      (node (ref "JP16") (pin "1") (pinfunction "1_1") (pintype "passive"))
      (node (ref "JP16") (pin "20") (pinfunction "20_20") (pintype "passive"))
      (node (ref "JP17") (pin "1") (pinfunction "1_1") (pintype "passive"))
      (node (ref "JP17") (pin "20") (pinfunction "20_20") (pintype "passive"))
      (node (ref "JP18") (pin "1") (pinfunction "1_1") (pintype "passive"))
      (node (ref "JP18") (pin "20") (pinfunction "20_20") (pintype "passive"))
      (node (ref "R1") (pin "1") (pinfunction "1_1") (pintype "passive"))
      (node (ref "R16") (pin "1") (pinfunction "1_1") (pintype "passive"))
      (node (ref "R18") (pin "2") (pinfunction "2_2") (pintype "passive"))
      (node (ref "R2") (pin "P$1") (pinfunction "1_P$1") (pintype "passive"))
      (node (ref "R23") (pin "2") (pinfunction "2_2") (pintype "passive"))
      (node (ref "R3") (pin "P$1") (pinfunction "1_P$1") (pintype "passive"))
      (node (ref "R6") (pin "2") (pinfunction "2_2") (pintype "passive"))
      (node (ref "RFBB") (pin "2") (pinfunction "2_2") (pintype "passive"))
      (node (ref "TP11") (pin "P$1") (pinfunction "P$1_P$1") (pintype "bidirectional"))
      (node (ref "TP12") (pin "P$1") (pinfunction "P$1_P$1") (pintype "bidirectional"))
      (node (ref "TP15") (pin "P$1") (pinfunction "P$1_P$1") (pintype "bidirectional"))
      (node (ref "TP5") (pin "P$1") (pinfunction "P$1_P$1") (pintype "bidirectional"))
      (node (ref "U$1") (pin "2") (pinfunction "S_2") (pintype "bidirectional"))
      (node (ref "U$3") (pin "P$6") (pinfunction "VSS_P$6") (pintype "bidirectional"))
      (node (ref "U$4") (pin "2") (pinfunction "2_2") (pintype "bidirectional"))
      (node (ref "U$5") (pin "2") (pinfunction "2_2") (pintype "bidirectional"))
      (node (ref "U1") (pin "2") (pinfunction "GND_2") (pintype "power_in"))
      (node (ref "X1") (pin "P$5") (pinfunction "1_P$5") (pintype "passive"))
      (node (ref "X2") (pin "P$4") (pinfunction "1_P$4") (pintype "passive"))
      (node (ref "X4") (pin "P$4") (pinfunction "1_P$4") (pintype "passive"))
      (node (ref "X5") (pin "GND") (pinfunction "GND_GND") (pintype "bidirectional"))
      (node (ref "X7") (pin "P$5") (pinfunction "1_P$5") (pintype "passive"))
    )
    (net (code "48") (name "Net-(A-PadP$1)") (class "Default")
      (node (ref "A") (pin "P$1") (pinfunction "P$1_P$1") (pintype "bidirectional"))
      (node (ref "AH") (pin "S@1") (pinfunction "S_S@1") (pintype "bidirectional"))
      (node (ref "AH") (pin "S@2") (pinfunction "S_S@2") (pintype "bidirectional"))
      (node (ref "AH") (pin "S@3") (pinfunction "S_S@3") (pintype "bidirectional"))
      (node (ref "AL") (pin "D@1") (pinfunction "D_D@1") (pintype "bidirectional"))
      (node (ref "AL") (pin "DTOP") (pinfunction "D_DTOP") (pintype "bidirectional"))
      (node (ref "D8") (pin "A") (pinfunction "A_A") (pintype "passive"))
      (node (ref "D9") (pin "C") (pinfunction "C_C") (pintype "passive"))
      (node (ref "R15") (pin "2") (pinfunction "2_2") (pintype "passive"))
      (node (ref "TP9") (pin "P$1") (pinfunction "P$1_P$1") (pintype "bidirectional"))
    )
    (net (code "49") (name "Net-(AH-PadG)") (class "Default")
      (node (ref "AH") (pin "G") (pinfunction "G_G") (pintype "bidirectional"))
      (node (ref "R12") (pin "2") (pinfunction "2_2") (pintype "passive"))
    )
    (net (code "50") (name "Net-(AL-PadG)") (class "Default")
      (node (ref "AL") (pin "G") (pinfunction "G_G") (pintype "bidirectional"))
      (node (ref "R11") (pin "2") (pinfunction "2_2") (pintype "passive"))
    )
    (net (code "51") (name "Net-(B-PadP$1)") (class "Default")
      (node (ref "B") (pin "P$1") (pinfunction "P$1_P$1") (pintype "bidirectional"))
      (node (ref "BH") (pin "S@1") (pinfunction "S_S@1") (pintype "bidirectional"))
      (node (ref "BH") (pin "S@2") (pinfunction "S_S@2") (pintype "bidirectional"))
      (node (ref "BH") (pin "S@3") (pinfunction "S_S@3") (pintype "bidirectional"))
      (node (ref "BL") (pin "D@1") (pinfunction "D_D@1") (pintype "bidirectional"))
      (node (ref "BL") (pin "DTOP") (pinfunction "D_DTOP") (pintype "bidirectional"))
      (node (ref "D10") (pin "A") (pinfunction "A_A") (pintype "passive"))
      (node (ref "D13") (pin "C") (pinfunction "C_C") (pintype "passive"))
      (node (ref "R14") (pin "2") (pinfunction "2_2") (pintype "passive"))
      (node (ref "TP13") (pin "P$1") (pinfunction "P$1_P$1") (pintype "bidirectional"))
    )
    (net (code "52") (name "Net-(BH-PadG)") (class "Default")
      (node (ref "BH") (pin "G") (pinfunction "G_G") (pintype "bidirectional"))
      (node (ref "R9") (pin "2") (pinfunction "2_2") (pintype "passive"))
    )
    (net (code "53") (name "Net-(BL-PadG)") (class "Default")
      (node (ref "BL") (pin "G") (pinfunction "G_G") (pintype "bidirectional"))
      (node (ref "R10") (pin "2") (pinfunction "2_2") (pintype "passive"))
    )
    (net (code "54") (name "Net-(C-PadP$1)") (class "Default")
      (node (ref "C") (pin "P$1") (pinfunction "P$1_P$1") (pintype "bidirectional"))
      (node (ref "CH") (pin "S@1") (pinfunction "S_S@1") (pintype "bidirectional"))
      (node (ref "CH") (pin "S@2") (pinfunction "S_S@2") (pintype "bidirectional"))
      (node (ref "CH") (pin "S@3") (pinfunction "S_S@3") (pintype "bidirectional"))
      (node (ref "CL") (pin "D@1") (pinfunction "D_D@1") (pintype "bidirectional"))
      (node (ref "CL") (pin "DTOP") (pinfunction "D_DTOP") (pintype "bidirectional"))
      (node (ref "D11") (pin "A") (pinfunction "A_A") (pintype "passive"))
      (node (ref "D12") (pin "C") (pinfunction "C_C") (pintype "passive"))
      (node (ref "R13") (pin "2") (pinfunction "2_2") (pintype "passive"))
      (node (ref "TP14") (pin "P$1") (pinfunction "P$1_P$1") (pintype "bidirectional"))
    )
    (net (code "55") (name "Net-(CH-PadG)") (class "Default")
      (node (ref "CH") (pin "G") (pinfunction "G_G") (pintype "bidirectional"))
      (node (ref "R7") (pin "2") (pinfunction "2_2") (pintype "passive"))
    )
    (net (code "56") (name "Net-(CL-PadG)") (class "Default")
      (node (ref "CL") (pin "G") (pinfunction "G_G") (pintype "bidirectional"))
      (node (ref "R8") (pin "2") (pinfunction "2_2") (pintype "passive"))
    )
    (net (code "57") (name "Net-(D2-K)") (class "Default")
      (node (ref "CBOOT") (pin "1") (pinfunction "1_1") (pintype "passive"))
      (node (ref "D2") (pin "1") (pinfunction "K_1") (pintype "passive"))
      (node (ref "L1") (pin "1") (pinfunction "1_1") (pintype "passive"))
      (node (ref "U1") (pin "6") (pinfunction "SW_6") (pintype "power_in"))
    )
    (net (code "58") (name "Net-(IC1-+IN)") (class "Default")
      (node (ref "IC1") (pin "3") (pinfunction "+IN_3") (pintype "input"))
      (node (ref "R5") (pin "2") (pinfunction "2_2") (pintype "passive"))
      (node (ref "R6") (pin "1") (pinfunction "1_1") (pintype "passive"))
    )
    (net (code "59") (name "Net-(IC1--IN)") (class "Default")
      (node (ref "IC1") (pin "2") (pinfunction "-IN_2") (pintype "input"))
      (node (ref "R17") (pin "2") (pinfunction "2_2") (pintype "passive"))
      (node (ref "R18") (pin "1") (pinfunction "1_1") (pintype "passive"))
    )
    (net (code "60") (name "Net-(IC2-VO)") (class "Default")
      (node (ref "IC2") (pin "3") (pinfunction "VO_3") (pintype "passive"))
      (node (ref "J1") (pin "1") (pinfunction "1_1") (pintype "passive"))
    )
    (net (code "61") (name "Net-(JP14-Pad14)") (class "Default")
      (node (ref "JP14") (pin "14") (pinfunction "14_14") (pintype "passive"))
      (node (ref "JP15") (pin "14") (pinfunction "14_14") (pintype "passive"))
      (node (ref "JP17") (pin "14") (pinfunction "14_14") (pintype "passive"))
    )
    (net (code "62") (name "Net-(JP14-Pad15)") (class "Default")
      (node (ref "JP14") (pin "15") (pinfunction "15_15") (pintype "passive"))
      (node (ref "JP15") (pin "15") (pinfunction "15_15") (pintype "passive"))
      (node (ref "JP17") (pin "15") (pinfunction "15_15") (pintype "passive"))
    )
    (net (code "63") (name "Net-(U$1-D)") (class "Default")
      (node (ref "J2") (pin "2") (pinfunction "2_2") (pintype "passive"))
      (node (ref "U$1") (pin "3") (pinfunction "D_3") (pintype "bidirectional"))
    )
    (net (code "64") (name "Net-(U$3-AHB)") (class "Default")
      (node (ref "D3") (pin "C") (pinfunction "C_C") (pintype "passive"))
      (node (ref "U$17") (pin "1") (pinfunction "1_1") (pintype "bidirectional"))
      (node (ref "U$3") (pin "P$16") (pinfunction "AHB_P$16") (pintype "bidirectional"))
    )
    (net (code "65") (name "Net-(U$3-BHB)") (class "Default")
      (node (ref "D1") (pin "C") (pinfunction "C_C") (pintype "passive"))
      (node (ref "U$15") (pin "1") (pinfunction "1_1") (pintype "bidirectional"))
      (node (ref "U$3") (pin "P$1") (pinfunction "BHB_P$1") (pintype "bidirectional"))
    )
    (net (code "66") (name "Net-(U$3-CHB)") (class "Default")
      (node (ref "D4") (pin "C") (pinfunction "C_C") (pintype "passive"))
      (node (ref "U$16") (pin "1") (pinfunction "1_1") (pintype "bidirectional"))
      (node (ref "U$3") (pin "P$13") (pinfunction "CHB_P$13") (pintype "bidirectional"))
    )
    (net (code "67") (name "Net-(U$3-RFSH)") (class "Default")
      (node (ref "U$3") (pin "P$9") (pinfunction "RFSH_P$9") (pintype "bidirectional"))
      (node (ref "U$5") (pin "1") (pinfunction "1_1") (pintype "bidirectional"))
    )
    (net (code "68") (name "Net-(U1-CB)") (class "Default")
      (node (ref "CBOOT") (pin "2") (pinfunction "2_2") (pintype "passive"))
      (node (ref "U1") (pin "1") (pinfunction "CB_1") (pintype "output"))
    )
    (net (code "69") (name "Net-(U1-FB)") (class "Default")
      (node (ref "RFBB") (pin "1") (pinfunction "1_1") (pintype "passive"))
      (node (ref "RFBT") (pin "2") (pinfunction "2_2") (pintype "passive"))
      (node (ref "U1") (pin "3") (pinfunction "FB_3") (pintype "input"))
    )
    (net (code "70") (name "VMOT") (class "Default")
      (node (ref "+") (pin "P$1") (pinfunction "P$1_P$1") (pintype "bidirectional"))
      (node (ref "AH") (pin "D@1") (pinfunction "D_D@1") (pintype "bidirectional"))
      (node (ref "AH") (pin "DTOP") (pinfunction "D_DTOP") (pintype "bidirectional"))
      (node (ref "BH") (pin "D@1") (pinfunction "D_D@1") (pintype "bidirectional"))
      (node (ref "BH") (pin "DTOP") (pinfunction "D_DTOP") (pintype "bidirectional"))
      (node (ref "C1") (pin "+") (pinfunction "+_+") (pintype "passive"))
      (node (ref "C4") (pin "+") (pinfunction "+_+") (pintype "passive"))
      (node (ref "CH") (pin "D@1") (pinfunction "D_D@1") (pintype "bidirectional"))
      (node (ref "CH") (pin "DTOP") (pinfunction "D_DTOP") (pintype "bidirectional"))
      (node (ref "CIN") (pin "1") (pinfunction "1_1") (pintype "passive"))
      (node (ref "D10") (pin "C") (pinfunction "C_C") (pintype "passive"))
      (node (ref "D11") (pin "C") (pinfunction "C_C") (pintype "passive"))
      (node (ref "D8") (pin "C") (pinfunction "C_C") (pintype "passive"))
      (node (ref "U1") (pin "5") (pinfunction "VIN_5") (pintype "power_in"))
    )
    (net (code "71") (name "unconnected-(U$3-UVLO-PadP$8)") (class "Default")
      (node (ref "U$3") (pin "P$8") (pinfunction "UVLO_P$8") (pintype "bidirectional"))
    )
    (net (code "72") (name "unconnected-(U1-SHDN_N-Pad4)") (class "Default")
      (node (ref "U1") (pin "4") (pinfunction "SHDN_N_4") (pintype "input"))
    )
  )
)
